# bridge.net
KiCad netlist of a schematic drawn in EAGLE
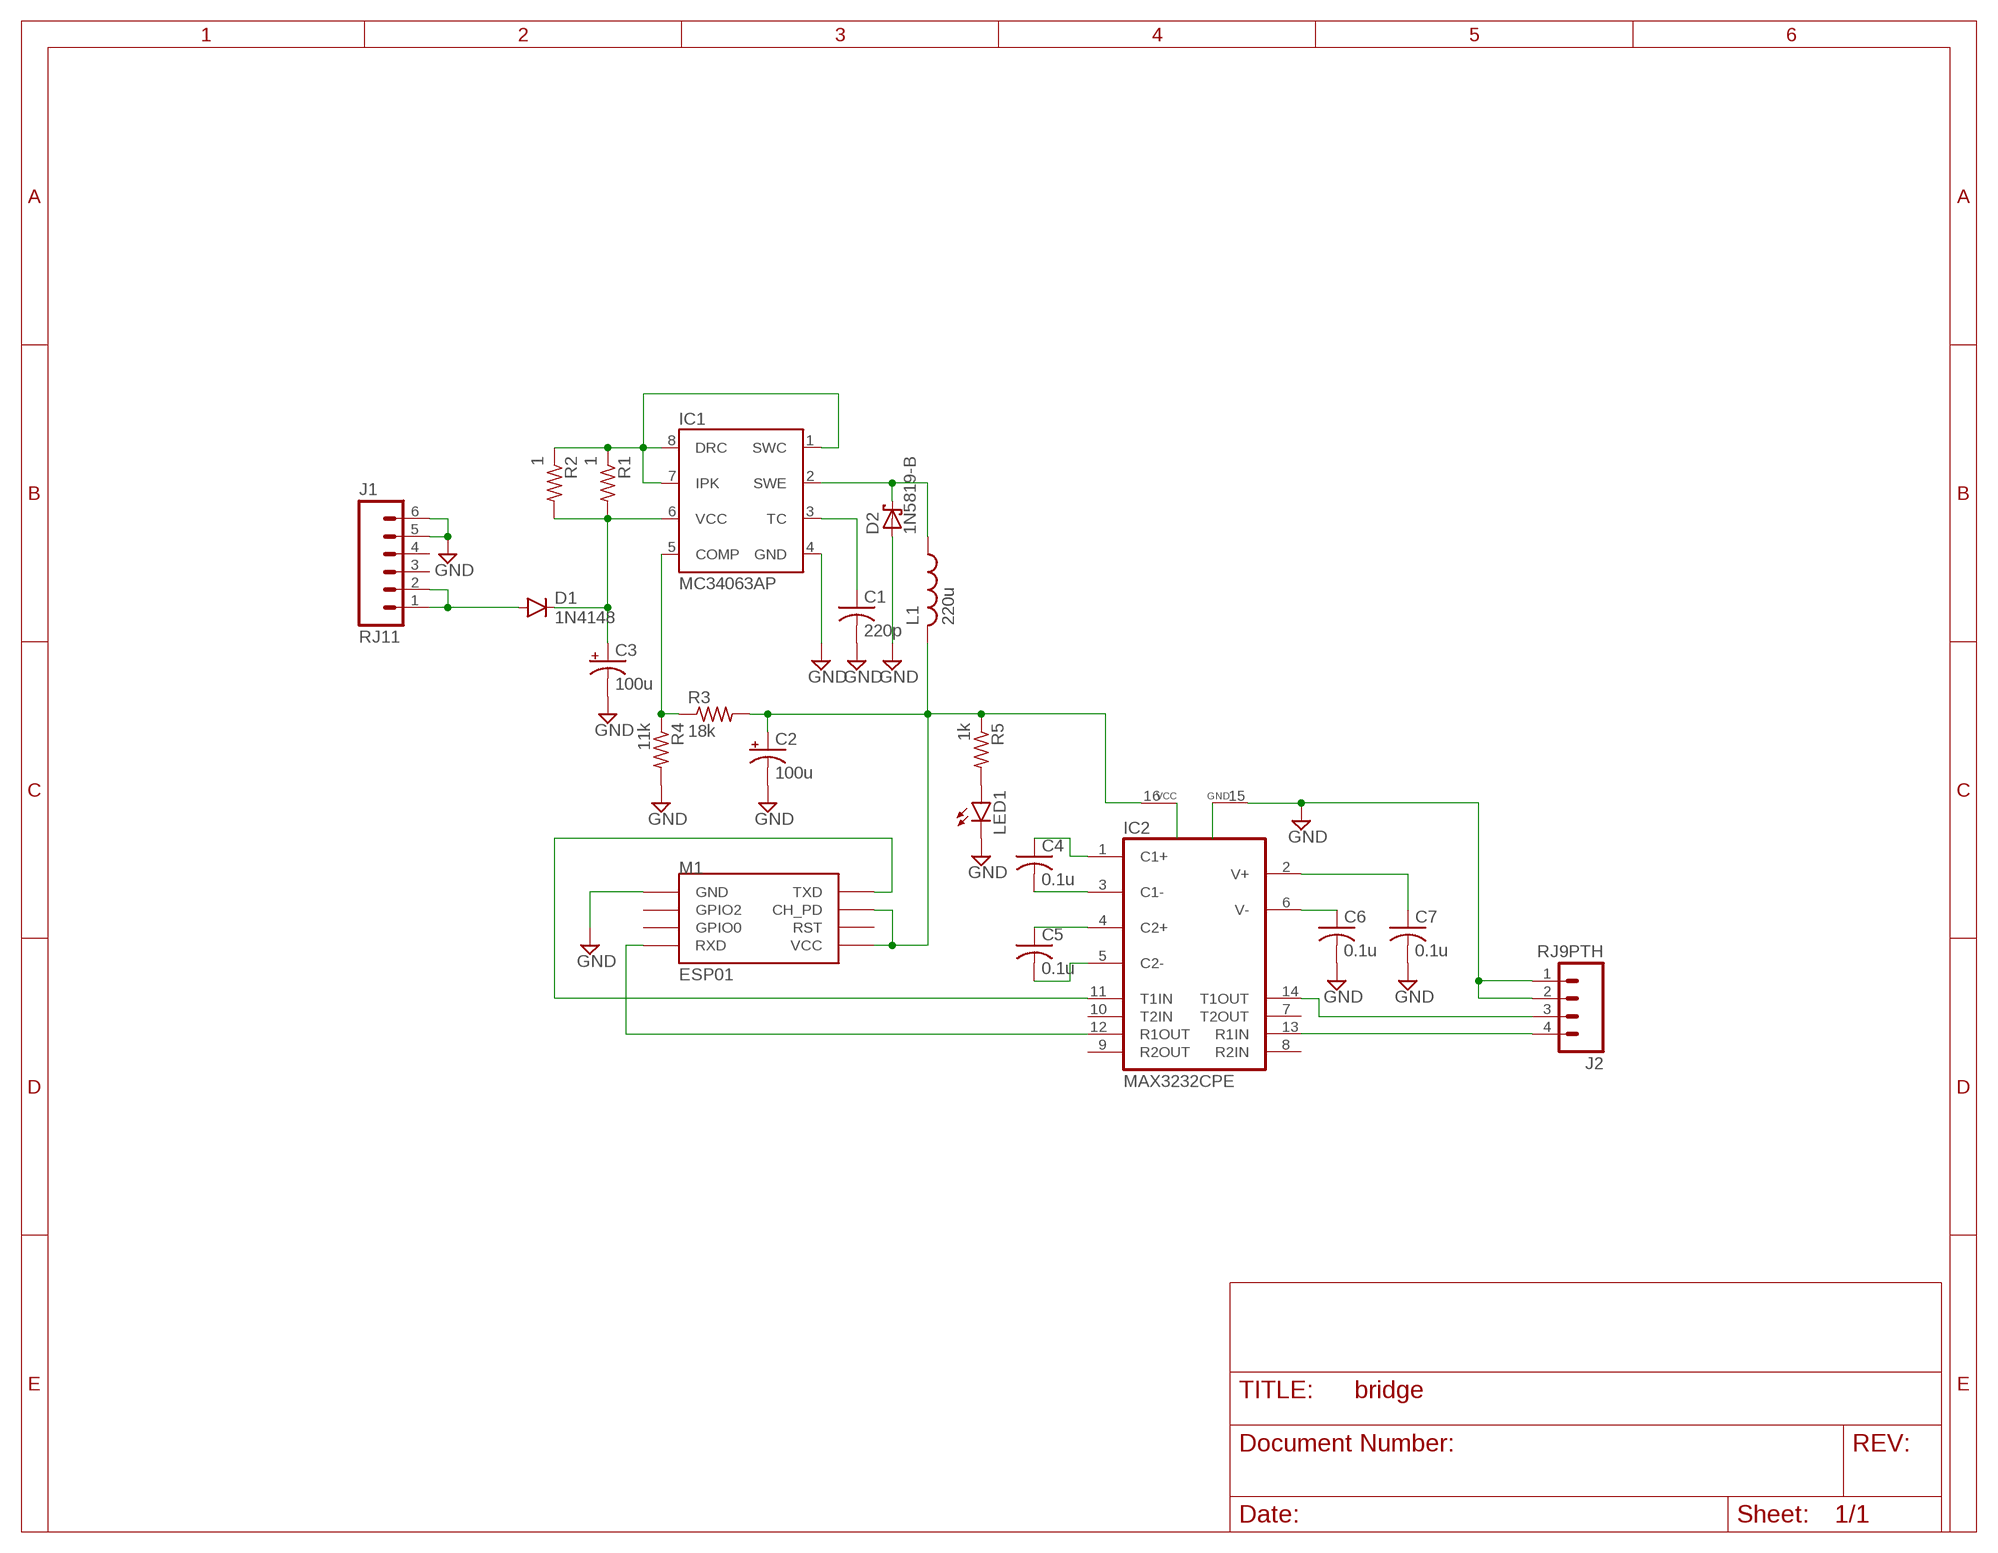
[diagram p0: schematic, sheet 1]

(export (version "E")
  (design (tool "Eeschema 10.0.6"))
  (components
    (comp (ref "C1")
      (value "220p")
      (footprint "eagle-import:C025-024X044")
      (libsource (lib "eagle-import") (part "C-US025-024X044"))
    )
    (comp (ref "C2")
      (value "100u")
      (footprint "eagle-import:E2,5-6")
      (libsource (lib "eagle-import") (part "CPOL-USE2.5-6"))
    )
    (comp (ref "C3")
      (value "100u")
      (footprint "eagle-import:E2,5-6E")
      (libsource (lib "eagle-import") (part "CPOL-USE2,5-6E"))
    )
    (comp (ref "C4")
      (value "0.1u")
      (footprint "eagle-import:C025-024X044")
      (libsource (lib "eagle-import") (part "C-US025-024X044"))
    )
    (comp (ref "C5")
      (value "0.1u")
      (footprint "eagle-import:C025-024X044")
      (libsource (lib "eagle-import") (part "C-US025-024X044"))
    )
    (comp (ref "C6")
      (value "0.1u")
      (footprint "eagle-import:C025-024X044")
      (libsource (lib "eagle-import") (part "C-US025-024X044"))
    )
    (comp (ref "C7")
      (value "0.1u")
      (footprint "eagle-import:C025-024X044")
      (libsource (lib "eagle-import") (part "C-US025-024X044"))
    )
    (comp (ref "D1")
      (value "1N4148")
      (footprint "eagle-import:DIODE-1N4148")
      (libsource (lib "eagle-import") (part "DIODE1N4148"))
    )
    (comp (ref "D2")
      (value "1N5819-B")
      (footprint "eagle-import:DO41-7.6")
      (libsource (lib "eagle-import") (part "1N5819-B"))
    )
    (comp (ref "IC1")
      (value "MC34063AP")
      (footprint "eagle-import:DIL-08")
      (libsource (lib "eagle-import") (part "MC34063AP"))
    )
    (comp (ref "IC2")
      (value "MAX3232CPE")
      (footprint "eagle-import:DIL16")
      (fields (field (name "MF") "MAXIM") (field (name "MPN") "MAX3232CPE+"))
      (libsource (lib "eagle-import") (part "MAX3232PEC"))
    )
    (comp (ref "J1")
      (value "RJ11")
      (footprint "eagle-import:RJ11-6")
      (libsource (lib "eagle-import") (part "RJ11-6PTH"))
    )
    (comp (ref "J2")
      (value "RJ9PTH")
      (footprint "eagle-import:RJ9")
      (libsource (lib "eagle-import") (part "RJ9PTH"))
    )
    (comp (ref "L1")
      (value "220u")
      (footprint "eagle-import:6000-XXXX-RC")
      (libsource (lib "eagle-import") (part "L-US6000-XXX-RC"))
    )
    (comp (ref "LED1")
      (value "LED5MM")
      (footprint "eagle-import:LED5MM")
      (libsource (lib "eagle-import") (part "LED5MM"))
    )
    (comp (ref "M1")
      (value "ESP01")
      (footprint "eagle-import:ESP01")
      (libsource (lib "eagle-import") (part "ESP01"))
    )
    (comp (ref "R1")
      (value "1")
      (footprint "eagle-import:0204V")
      (libsource (lib "eagle-import") (part "R-US_0204/2V"))
    )
    (comp (ref "R2")
      (value "1")
      (footprint "eagle-import:0204V")
      (libsource (lib "eagle-import") (part "R-US_0204/2V"))
    )
    (comp (ref "R3")
      (value "18k")
      (footprint "eagle-import:0204V")
      (libsource (lib "eagle-import") (part "R-US_0204/2V"))
    )
    (comp (ref "R4")
      (value "11k")
      (footprint "eagle-import:0204V")
      (libsource (lib "eagle-import") (part "R-US_0204/2V"))
    )
    (comp (ref "R5")
      (value "1k")
      (footprint "eagle-import:0204_7")
      (libsource (lib "eagle-import") (part "R-US_0204/7"))
    )
  )
  (nets
    (net (code "1") (name "GND") (class "Default")
      (node (ref "C1") (pin "2") (pinfunction "2_2") (pintype "passive"))
      (node (ref "C2") (pin "-") (pinfunction "-_-") (pintype "passive"))
      (node (ref "C3") (pin "-") (pinfunction "-_-") (pintype "passive"))
      (node (ref "C6") (pin "2") (pinfunction "2_2") (pintype "passive"))
      (node (ref "C7") (pin "2") (pinfunction "2_2") (pintype "passive"))
      (node (ref "D2") (pin "A") (pinfunction "A_A") (pintype "passive"))
      (node (ref "IC1") (pin "4") (pinfunction "GND_4") (pintype "power_in"))
      (node (ref "IC2") (pin "15") (pinfunction "GND_15") (pintype "power_in"))
      (node (ref "J1") (pin "5") (pinfunction "5_5") (pintype "passive"))
      (node (ref "J1") (pin "6") (pinfunction "6_6") (pintype "passive"))
      (node (ref "J2") (pin "1") (pinfunction "1_1") (pintype "passive"))
      (node (ref "J2") (pin "2") (pinfunction "2_2") (pintype "passive"))
      (node (ref "LED1") (pin "K") (pinfunction "C_K") (pintype "passive"))
      (node (ref "M1") (pin "GND") (pinfunction "GND_GND") (pintype "bidirectional"))
      (node (ref "R4") (pin "2") (pinfunction "2_2") (pintype "passive"))
    )
    (net (code "2") (name "Net-(D1-PadA)") (class "Default")
      (node (ref "D1") (pin "A") (pinfunction "A_A") (pintype "passive"))
      (node (ref "J1") (pin "1") (pinfunction "1_1") (pintype "passive"))
      (node (ref "J1") (pin "2") (pinfunction "2_2") (pintype "passive"))
    )
    (net (code "3") (name "Net-(IC1-COMP)") (class "Default")
      (node (ref "IC1") (pin "5") (pinfunction "COMP_5") (pintype "input"))
      (node (ref "R3") (pin "1") (pinfunction "1_1") (pintype "passive"))
      (node (ref "R4") (pin "1") (pinfunction "1_1") (pintype "passive"))
    )
    (net (code "4") (name "Net-(IC1-DRC)") (class "Default")
      (node (ref "IC1") (pin "1") (pinfunction "SWC_1") (pintype "bidirectional"))
      (node (ref "IC1") (pin "7") (pinfunction "IPK_7") (pintype "input"))
      (node (ref "IC1") (pin "8") (pinfunction "DRC_8") (pintype "input"))
      (node (ref "R1") (pin "1") (pinfunction "1_1") (pintype "passive"))
      (node (ref "R2") (pin "1") (pinfunction "1_1") (pintype "passive"))
    )
    (net (code "5") (name "Net-(IC1-SWE)") (class "Default")
      (node (ref "D2") (pin "C") (pinfunction "C_C") (pintype "passive"))
      (node (ref "IC1") (pin "2") (pinfunction "SWE_2") (pintype "bidirectional"))
      (node (ref "L1") (pin "1") (pinfunction "1_1") (pintype "passive"))
    )
    (net (code "6") (name "Net-(IC1-TC)") (class "Default")
      (node (ref "C1") (pin "1") (pinfunction "1_1") (pintype "passive"))
      (node (ref "IC1") (pin "3") (pinfunction "TC_3") (pintype "passive"))
    )
    (net (code "7") (name "Net-(IC1-VCC)") (class "Default")
      (node (ref "C3") (pin "+") (pinfunction "+_+") (pintype "passive"))
      (node (ref "D1") (pin "C") (pinfunction "C_C") (pintype "passive"))
      (node (ref "IC1") (pin "6") (pinfunction "VCC_6") (pintype "power_in"))
      (node (ref "R1") (pin "2") (pinfunction "2_2") (pintype "passive"))
      (node (ref "R2") (pin "2") (pinfunction "2_2") (pintype "passive"))
    )
    (net (code "8") (name "Net-(IC2A-C1+)") (class "Default")
      (node (ref "C4") (pin "1") (pinfunction "1_1") (pintype "passive"))
      (node (ref "IC2") (pin "1") (pinfunction "C1+_1") (pintype "bidirectional"))
    )
    (net (code "9") (name "Net-(IC2A-C1-)") (class "Default")
      (node (ref "C4") (pin "2") (pinfunction "2_2") (pintype "passive"))
      (node (ref "IC2") (pin "3") (pinfunction "C1-_3") (pintype "bidirectional"))
    )
    (net (code "10") (name "Net-(IC2A-C2+)") (class "Default")
      (node (ref "C5") (pin "1") (pinfunction "1_1") (pintype "passive"))
      (node (ref "IC2") (pin "4") (pinfunction "C2+_4") (pintype "bidirectional"))
    )
    (net (code "11") (name "Net-(IC2A-C2-)") (class "Default")
      (node (ref "C5") (pin "2") (pinfunction "2_2") (pintype "passive"))
      (node (ref "IC2") (pin "5") (pinfunction "C2-_5") (pintype "bidirectional"))
    )
    (net (code "12") (name "Net-(IC2A-R1IN)") (class "Default")
      (node (ref "IC2") (pin "13") (pinfunction "R1IN_13") (pintype "input"))
      (node (ref "J2") (pin "4") (pinfunction "4_4") (pintype "passive"))
    )
    (net (code "13") (name "Net-(IC2A-R1OUT)") (class "Default")
      (node (ref "IC2") (pin "12") (pinfunction "R1OUT_12") (pintype "output"))
      (node (ref "M1") (pin "RX") (pinfunction "RXD_RX") (pintype "bidirectional"))
    )
    (net (code "14") (name "Net-(IC2A-T1IN)") (class "Default")
      (node (ref "IC2") (pin "11") (pinfunction "T1IN_11") (pintype "input"))
      (node (ref "M1") (pin "TX") (pinfunction "TXD_TX") (pintype "bidirectional"))
    )
    (net (code "15") (name "Net-(IC2A-T1OUT)") (class "Default")
      (node (ref "IC2") (pin "14") (pinfunction "T1OUT_14") (pintype "output"))
      (node (ref "J2") (pin "3") (pinfunction "3_3") (pintype "passive"))
    )
    (net (code "16") (name "Net-(IC2A-V+)") (class "Default")
      (node (ref "C7") (pin "1") (pinfunction "1_1") (pintype "passive"))
      (node (ref "IC2") (pin "2") (pinfunction "V+_2") (pintype "bidirectional"))
    )
    (net (code "17") (name "Net-(IC2A-V-)") (class "Default")
      (node (ref "C6") (pin "1") (pinfunction "1_1") (pintype "passive"))
      (node (ref "IC2") (pin "6") (pinfunction "V-_6") (pintype "bidirectional"))
    )
    (net (code "18") (name "Net-(IC2B-VCC)") (class "Default")
      (node (ref "C2") (pin "+") (pinfunction "+_+") (pintype "passive"))
      (node (ref "IC2") (pin "16") (pinfunction "VCC_16") (pintype "power_in"))
      (node (ref "L1") (pin "2") (pinfunction "2_2") (pintype "passive"))
      (node (ref "M1") (pin "CH_PD") (pinfunction "CH_PD_CH_PD") (pintype "bidirectional"))
      (node (ref "M1") (pin "VCC") (pinfunction "VCC_VCC") (pintype "bidirectional"))
      (node (ref "R3") (pin "2") (pinfunction "2_2") (pintype "passive"))
      (node (ref "R5") (pin "1") (pinfunction "1_1") (pintype "passive"))
    )
    (net (code "19") (name "Net-(LED1-PadA)") (class "Default")
      (node (ref "LED1") (pin "A") (pinfunction "A_A") (pintype "passive"))
      (node (ref "R5") (pin "2") (pinfunction "2_2") (pintype "passive"))
    )
    (net (code "20") (name "unconnected-(IC2A-R2IN-Pad8)") (class "Default")
      (node (ref "IC2") (pin "8") (pinfunction "R2IN_8") (pintype "input"))
    )
    (net (code "21") (name "unconnected-(IC2A-R2OUT-Pad9)") (class "Default")
      (node (ref "IC2") (pin "9") (pinfunction "R2OUT_9") (pintype "output"))
    )
    (net (code "22") (name "unconnected-(IC2A-T2IN-Pad10)") (class "Default")
      (node (ref "IC2") (pin "10") (pinfunction "T2IN_10") (pintype "input"))
    )
    (net (code "23") (name "unconnected-(IC2A-T2OUT-Pad7)") (class "Default")
      (node (ref "IC2") (pin "7") (pinfunction "T2OUT_7") (pintype "output"))
    )
    (net (code "24") (name "unconnected-(J1-Pad3)") (class "Default")
      (node (ref "J1") (pin "3") (pinfunction "3_3") (pintype "passive"))
    )
    (net (code "25") (name "unconnected-(J1-Pad4)") (class "Default")
      (node (ref "J1") (pin "4") (pinfunction "4_4") (pintype "passive"))
    )
    (net (code "26") (name "unconnected-(M1-PadGPIO0)") (class "Default")
      (node (ref "M1") (pin "GPIO0") (pinfunction "GPIO0_GPIO0") (pintype "bidirectional"))
    )
    (net (code "27") (name "unconnected-(M1-PadGPIO2)") (class "Default")
      (node (ref "M1") (pin "GPIO2") (pinfunction "GPIO2_GPIO2") (pintype "bidirectional"))
    )
    (net (code "28") (name "unconnected-(M1-PadRST)") (class "Default")
      (node (ref "M1") (pin "RST") (pinfunction "RST_RST") (pintype "bidirectional"))
    )
  )
)
